# Brd_3_Golden_Ardunio_Schematic.net
KiCad netlist of a schematic drawn in Altium Designer
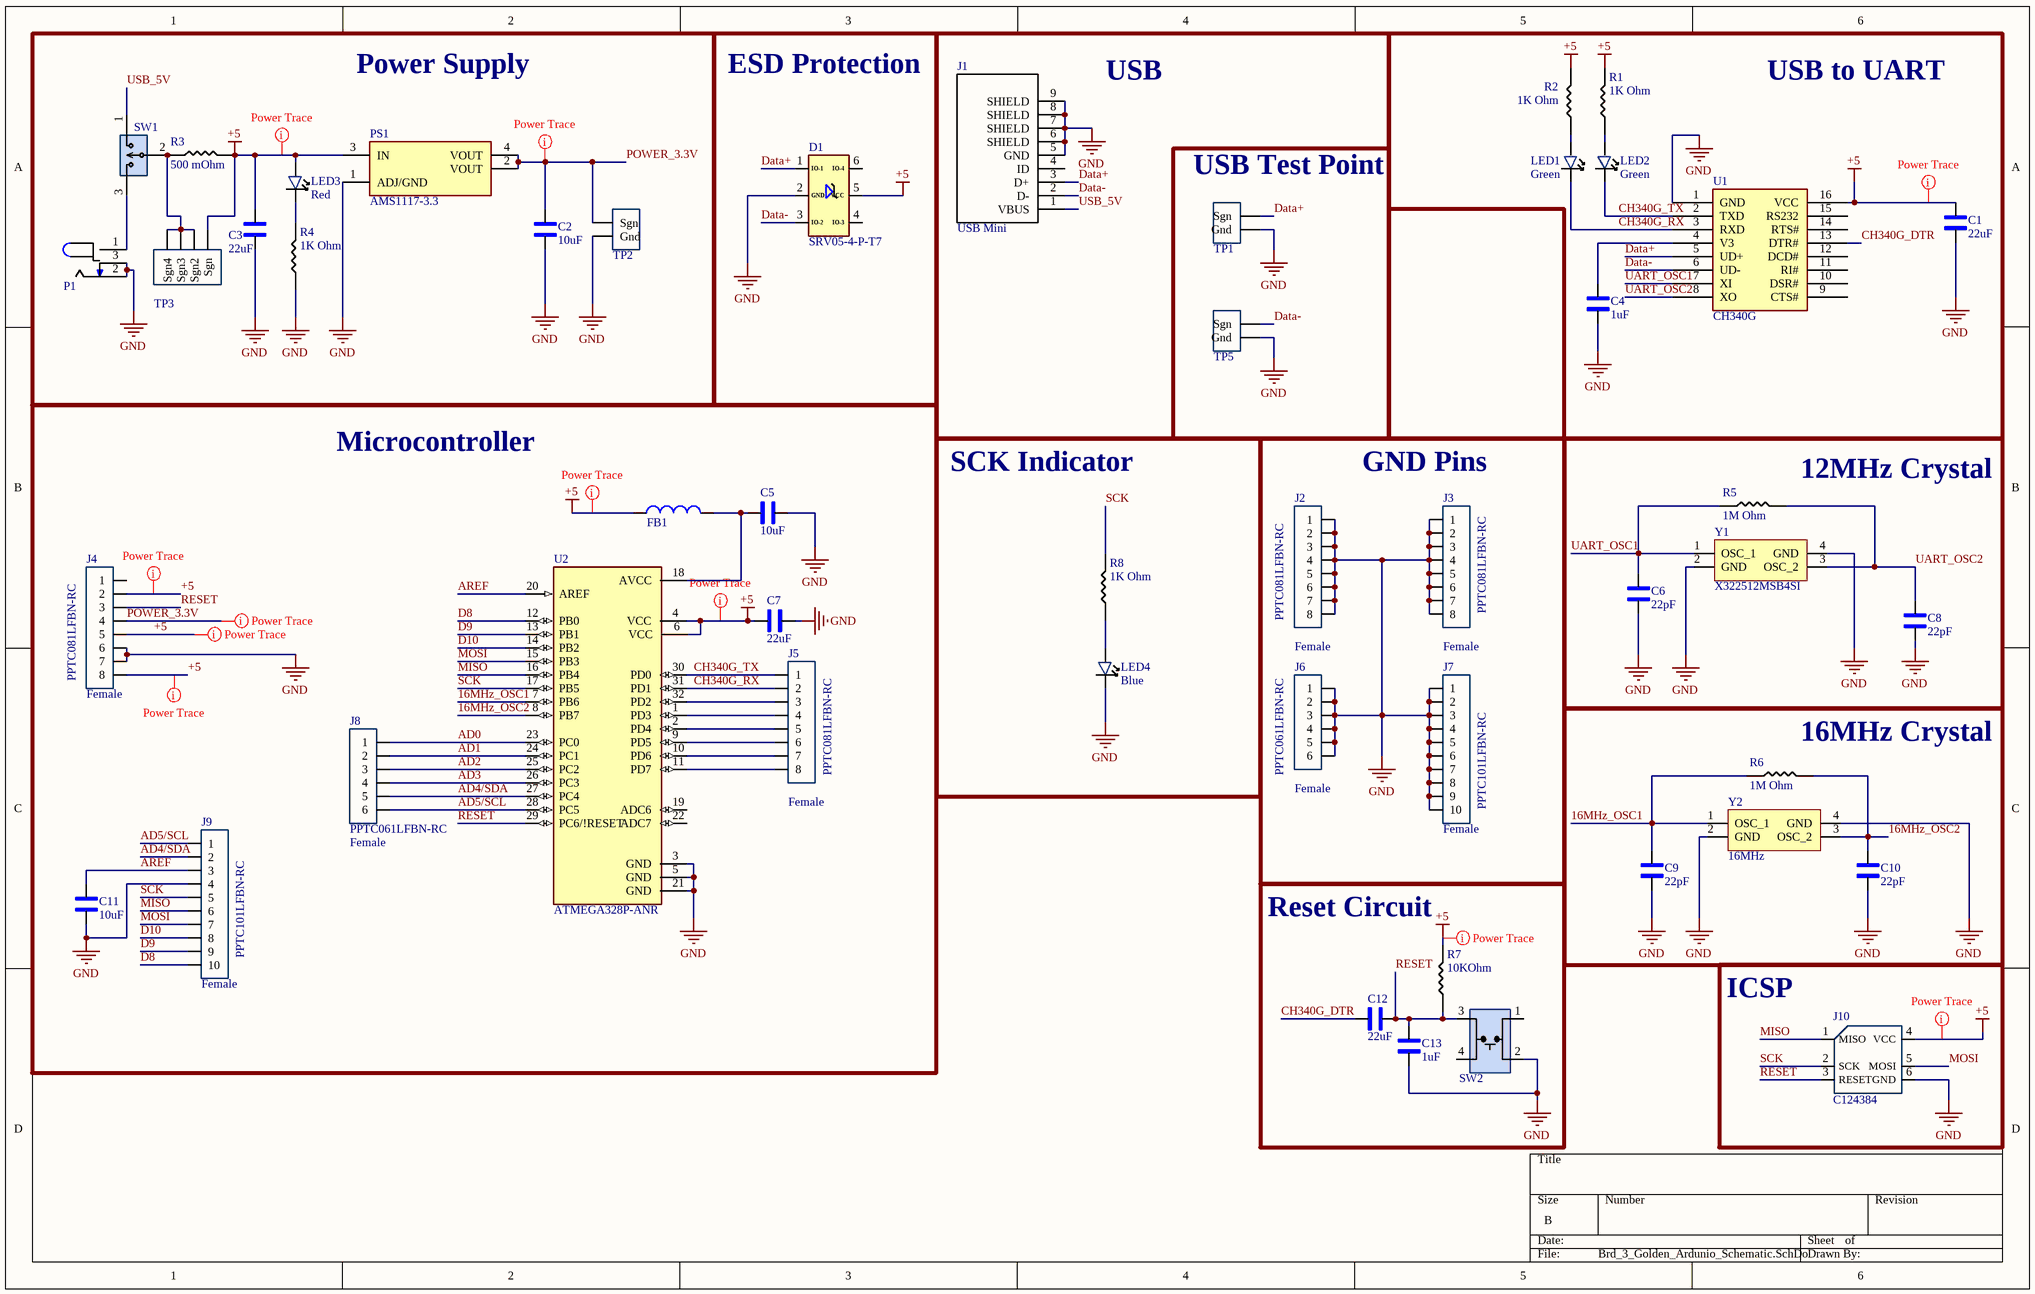
[diagram p0: Brd_3_Golden_Ardunio_Schematic.SchDoc]

(export (version "E")
  (design (tool "Eeschema 10.0.6"))
  (components
    (comp (ref "C1")
      (value "22uF")
      (footprint "0805_Passive_Capaciitor")
      (description "MULTILAYER CERAMIC CAPACITORS MLCC - SMD/SMT 22UF 25V 0805 ROHS")
      (fields (field (name "MFR PART #") "CL21A226MAQNNNE") (field (name "LCSC PART#") "C45783"))
      (libsource (lib "ECEN5730Lib_JLC_2021_08") (part "C_22uF_0805"))
    )
    (comp (ref "C2")
      (value "10uF")
      (footprint "0402_Passive_Capacitor")
      (description "10uF ±20% 6.3V X5R 0402 Multilayer Ceramic Capacitors MLCC - SMD/SMT RoHS")
      (fields (field (name "MFR PART #") "CL05A106MQ5NUNC") (field (name "LCSC PART#") "C15525"))
      (libsource (lib "ECEN5730Lib_JLC_2021_08") (part "C_10uF_0402"))
    )
    (comp (ref "C3")
      (value "22uF")
      (footprint "0805_Passive_Capaciitor")
      (description "MULTILAYER CERAMIC CAPACITORS MLCC - SMD/SMT 22UF 25V 0805 ROHS")
      (fields (field (name "MFR PART #") "CL21A226MAQNNNE") (field (name "LCSC PART#") "C45783"))
      (libsource (lib "ECEN5730Lib_JLC_2021_08") (part "C_22uF_0805"))
    )
    (comp (ref "C4")
      (value "1uF")
      (footprint "0402_Passive_Capacitor")
      (description "MULTILAYER CERAMIC CAPACITORS MLCC - SMD/SMT 1UF 25V 0402 ROHS")
      (fields (field (name "MFR PART #") "CL05A105KA5NQNC") (field (name "LCSC PART#") "C52923"))
      (libsource (lib "ECEN5730Lib_JLC_2021_08") (part "C_1uF_0402"))
    )
    (comp (ref "C5")
      (value "10uF")
      (footprint "0402_Passive_Capacitor")
      (description "10uF ±20% 6.3V X5R 0402 Multilayer Ceramic Capacitors MLCC - SMD/SMT RoHS")
      (fields (field (name "MFR PART #") "CL05A106MQ5NUNC") (field (name "LCSC PART#") "C15525"))
      (libsource (lib "ECEN5730Lib_JLC_2021_08") (part "C_10uF_0402"))
    )
    (comp (ref "C6")
      (value "22pF")
      (footprint "0402_Passive_Capacitor")
      (description "MULTILAYER CERAMIC CAPACITORS MLCC - SMD/SMT 22PF 50V 0402 ROHS")
      (fields (field (name "MFR PART #") "0402CG220J500NT") (field (name "LCSC PART#") "C1555"))
      (libsource (lib "ECEN5730Lib_JLC_2021_08") (part "C_22pF_0402"))
    )
    (comp (ref "C7")
      (value "22uF")
      (footprint "0805_Passive_Capaciitor")
      (description "MULTILAYER CERAMIC CAPACITORS MLCC - SMD/SMT 22UF 25V 0805 ROHS")
      (fields (field (name "MFR PART #") "CL21A226MAQNNNE") (field (name "LCSC PART#") "C45783"))
      (libsource (lib "ECEN5730Lib_JLC_2021_08") (part "C_22uF_0805"))
    )
    (comp (ref "C8")
      (value "22pF")
      (footprint "0402_Passive_Capacitor")
      (description "MULTILAYER CERAMIC CAPACITORS MLCC - SMD/SMT 22PF 50V 0402 ROHS")
      (fields (field (name "MFR PART #") "0402CG220J500NT") (field (name "LCSC PART#") "C1555"))
      (libsource (lib "ECEN5730Lib_JLC_2021_08") (part "C_22pF_0402"))
    )
    (comp (ref "C9")
      (value "22pF")
      (footprint "0402_Passive_Capacitor")
      (description "MULTILAYER CERAMIC CAPACITORS MLCC - SMD/SMT 22PF 50V 0402 ROHS")
      (fields (field (name "MFR PART #") "0402CG220J500NT") (field (name "LCSC PART#") "C1555"))
      (libsource (lib "ECEN5730Lib_JLC_2021_08") (part "C_22pF_0402"))
    )
    (comp (ref "C10")
      (value "22pF")
      (footprint "0402_Passive_Capacitor")
      (description "MULTILAYER CERAMIC CAPACITORS MLCC - SMD/SMT 22PF 50V 0402 ROHS")
      (fields (field (name "MFR PART #") "0402CG220J500NT") (field (name "LCSC PART#") "C1555"))
      (libsource (lib "ECEN5730Lib_JLC_2021_08") (part "C_22pF_0402"))
    )
    (comp (ref "C11")
      (value "10uF")
      (footprint "0402_Passive_Capacitor")
      (description "10uF ±20% 6.3V X5R 0402 Multilayer Ceramic Capacitors MLCC - SMD/SMT RoHS")
      (fields (field (name "MFR PART #") "CL05A106MQ5NUNC") (field (name "LCSC PART#") "C15525"))
      (libsource (lib "ECEN5730Lib_JLC_2021_08") (part "C_10uF_0402"))
    )
    (comp (ref "C12")
      (value "22uF")
      (footprint "0805_Passive_Capaciitor")
      (description "MULTILAYER CERAMIC CAPACITORS MLCC - SMD/SMT 22UF 25V 0805 ROHS")
      (fields (field (name "MFR PART #") "CL21A226MAQNNNE") (field (name "LCSC PART#") "C45783"))
      (libsource (lib "ECEN5730Lib_JLC_2021_08") (part "C_22uF_0805"))
    )
    (comp (ref "C13")
      (value "1uF")
      (footprint "0402_Passive_Capacitor")
      (description "MULTILAYER CERAMIC CAPACITORS MLCC - SMD/SMT 1UF 25V 0402 ROHS")
      (fields (field (name "MFR PART #") "CL05A105KA5NQNC") (field (name "LCSC PART#") "C52923"))
      (libsource (lib "ECEN5730Lib_JLC_2021_08") (part "C_1uF_0402"))
    )
    (comp (ref "D1")
      (value "SRV05-4-P-T7")
      (footprint "TVS")
      (description "TVS SOT-23-6 ROHS")
      (fields (field (name "LCSC PART#") "C85364"))
      (libsource (lib "ECEN5730Lib_JLC_2021_08") (part "D_TVS_Diode"))
    )
    (comp (ref "FB1")
      (value "FB_10uH_0603")
      (footprint "0603_PASSIVE_Capacitor")
      (fields (field (name "MFR PART #") "SDFL1608S100KTF") (field (name "LCSC PART#") "C1035"))
      (libsource (lib "ECEN5730Lib_JLC_2021_08") (part "FB_10uH_0603"))
    )
    (comp (ref "J1")
      (value "USB Mini")
      (footprint "USB_MINI_B")
      (description "Through Hole USB Connectors RoHS")
      (fields (field (name "LCSC PART#") "C46398") (field (name "MFR PART #") "920-462A2021D10102"))
      (libsource (lib "ECEN5730Lib_JLC_2021_08") (part "J_USB_B_Mini"))
    )
    (comp (ref "J2")
      (value "PPTC081LFBN-RC")
      (footprint "8_PIN_ARDUINO_100MIL")
      (description "8 Position Header Connector 0.100\" (2.54mm) Through Hole Tin")
      (fields
        (field (name "DIGIKEY PART") "S7006-ND")
        (field (name "LCSC PART#") "C27438")
        (field (name "ALTIUM_VALUE") "Female")
      )
      (libsource (lib "") (part "JF_8_PIN_FEMALE_ARDUINO_1"))
    )
    (comp (ref "J3")
      (value "PPTC081LFBN-RC")
      (footprint "8_PIN_ARDUINO_100MIL")
      (description "8 Position Header Connector 0.100\" (2.54mm) Through Hole Tin")
      (fields
        (field (name "DIGIKEY PART") "S7006-ND")
        (field (name "LCSC PART#") "C27438")
        (field (name "ALTIUM_VALUE") "Female")
      )
      (libsource (lib "ECEN5730Lib_JLC_2021_08") (part "JF_8_PIN_FEMALE_ARDUINO"))
    )
    (comp (ref "J4")
      (value "PPTC081LFBN-RC")
      (footprint "8_PIN_ARDUINO_100MIL")
      (description "8 Position Header Connector 0.100\" (2.54mm) Through Hole Tin")
      (fields
        (field (name "DIGIKEY PART") "S7006-ND")
        (field (name "LCSC PART#") "C27438")
        (field (name "ALTIUM_VALUE") "Female")
      )
      (libsource (lib "") (part "JF_8_PIN_FEMALE_ARDUINO_1"))
    )
    (comp (ref "J5")
      (value "PPTC081LFBN-RC")
      (footprint "8_PIN_ARDUINO_100MIL")
      (description "8 Position Header Connector 0.100\" (2.54mm) Through Hole Tin")
      (fields
        (field (name "DIGIKEY PART") "S7006-ND")
        (field (name "LCSC PART#") "C27438")
        (field (name "ALTIUM_VALUE") "Female")
      )
      (libsource (lib "ECEN5730Lib_JLC_2021_08") (part "JF_8_PIN_FEMALE_ARDUINO"))
    )
    (comp (ref "J6")
      (value "PPTC061LFBN-RC")
      (footprint "6_PIN_ARDUINO_100mil")
      (description "6 Position Header Connector 0.100\" (2.54mm) Through Hole Tin")
      (fields
        (field (name "DIGIKEY PART") "S7004-ND")
        (field (name "LCSC PART#") "C40877")
        (field (name "ALTIUM_VALUE") "Female")
      )
      (libsource (lib "ECEN5730Lib_JLC_2021_08") (part "JF_6_PIN_FEMALE_ARDUINO"))
    )
    (comp (ref "J7")
      (value "PPTC101LFBN-RC")
      (footprint "10_PIN_ARDUINO_100MIL")
      (description "10 Position Header Connector 0.100\" (2.54mm) Through Hole Tin")
      (fields
        (field (name "DIGIKEY PART") "S7008-ND")
        (field (name "LCSC PART#") "C225507")
        (field (name "ALTIUM_VALUE") "Female")
      )
      (libsource (lib "ECEN5730Lib_JLC_2021_08") (part "JF_10_PIN_FEMALE_ARDUINO"))
    )
    (comp (ref "J8")
      (value "PPTC061LFBN-RC")
      (footprint "6_PIN_ARDUINO_100mil")
      (description "6 Position Header Connector 0.100\" (2.54mm) Through Hole Tin")
      (fields
        (field (name "DIGIKEY PART") "S7004-ND")
        (field (name "LCSC PART#") "C40877")
        (field (name "ALTIUM_VALUE") "Female")
      )
      (libsource (lib "ECEN5730Lib_JLC_2021_08") (part "JF_6_PIN_FEMALE_ARDUINO"))
    )
    (comp (ref "J9")
      (value "PPTC101LFBN-RC")
      (footprint "10_PIN_ARDUINO_100MIL")
      (description "10 Position Header Connector 0.100\" (2.54mm) Through Hole Tin")
      (fields
        (field (name "DIGIKEY PART") "S7008-ND")
        (field (name "LCSC PART#") "C225507")
        (field (name "ALTIUM_VALUE") "Female")
      )
      (libsource (lib "ECEN5730Lib_JLC_2021_08") (part "JF_10_PIN_FEMALE_ARDUINO"))
    )
    (comp (ref "J10")
      (value "NRPN032PAEN-RC")
      (footprint "ICSP")
      (description "Connector Header Through Hole 6 position 0.079\" (2.00mm)")
      (fields (field (name "DIGIKEY PART") "S5801-03-ND") (field (name "LCSC PART#") "C124384"))
      (libsource (lib "ECEN5730Lib_JLC_2021_08") (part "J_ICSP"))
    )
    (comp (ref "LED1")
      (value "Green")
      (footprint "LED_0603")
      (description "LIGHT EMITTING DIODES (LED) GREEN 520~535NM 112~258MCD@20MA TOP VIEW 0603 ROHS")
      (fields (field (name "MFR PART #") "19-217/GHC-YR1S2/3T") (field (name "LCSC PART#") "C72043"))
      (libsource (lib "ECEN5730Lib_JLC_2021_08") (part "LED_GREEN_0603"))
    )
    (comp (ref "LED2")
      (value "Green")
      (footprint "LED_0603")
      (description "LIGHT EMITTING DIODES (LED) GREEN 520~535NM 112~258MCD@20MA TOP VIEW 0603 ROHS")
      (fields (field (name "MFR PART #") "19-217/GHC-YR1S2/3T") (field (name "LCSC PART#") "C72043"))
      (libsource (lib "ECEN5730Lib_JLC_2021_08") (part "LED_GREEN_0603"))
    )
    (comp (ref "LED3")
      (value "Red")
      (footprint "LED_0603")
      (description "LIGHT EMITTING DIODES (LED) RED 520~625NM 90~100MCD@20MA TOP VIEW 0603 ROHS")
      (fields (field (name "MFR PART #") "KT-0603R") (field (name "LCSC PART#") "C2286"))
      (libsource (lib "ECEN5730Lib_JLC_2021_08") (part "LED_RED_0603"))
    )
    (comp (ref "LED4")
      (value "Blue")
      (footprint "LED_0603")
      (description "LIGHT EMITTING DIODES (LED) BLUE 465~475NM 11.5~28.5MCD@5MA TOP VIEW 0603 ROHS")
      (fields (field (name "MFR PART #") "19-217/BHC-ZL1M2RY/3T") (field (name "LCSC PART#") "C72041"))
      (libsource (lib "ECEN5730Lib_JLC_2021_08") (part "LED_BLUE_0603"))
    )
    (comp (ref "P1")
      (value "Power Jack")
      (footprint "Power_Jack")
      (description "Power Barrel Connector Jack 2.10mm ID (0.083\"), 5.50mm OD (0.217\") Through Hole, Right Angle")
      (fields (field (name "DIGIKEY PART") "CP-102A-ND") (field (name "LCSC PART#") "C136744"))
      (libsource (lib "ECEN5730Lib_JLC_2021_08") (part "P_Power Jack"))
    )
    (comp (ref "PS1")
      (value "AMS1117-3.3")
      (footprint "LDO")
      (description "LOW DROPOUT REGULATORS(LDO) POSITIVE FIXED 1.3V @ 800MA 15V 3.3V 1A SOT-223 ROHS")
      (fields (field (name "LCSC PART#") "C6186"))
      (libsource (lib "ECEN5730Lib_JLC_2021_08") (part "PS_AMS_LDO_3v3"))
    )
    (comp (ref "R1")
      (value "1K Ohm")
      (footprint "0402_Passive_Resistor")
      (description "1 kOhms chip resistor SURFACE MOUNT 1KOHMS ±1% 1/16W 0402 ROHS")
      (fields (field (name "MFR PART #") "0402WGF1001TCE") (field (name "LCSC PART#") "C11702"))
      (libsource (lib "ECEN5730Lib_JLC_2021_08") (part "R_1K_0402"))
    )
    (comp (ref "R2")
      (value "1K Ohm")
      (footprint "0402_Passive_Resistor")
      (description "1 kOhms chip resistor SURFACE MOUNT 1KOHMS ±1% 1/16W 0402 ROHS")
      (fields (field (name "MFR PART #") "0402WGF1001TCE") (field (name "LCSC PART#") "C11702"))
      (libsource (lib "ECEN5730Lib_JLC_2021_08") (part "R_1K_0402"))
    )
    (comp (ref "R3")
      (value "500 mOhm")
      (footprint "0603_PASSIVE_Resistor")
      (description "CHIP RESISTOR - SURFACE MOUNT 0.5OHMS ±1% 1/10W 0603 ROHS")
      (fields (field (name "MFR PART #") "0603WAF500LT5E") (field (name "LCSC PART#") "C45312"))
      (libsource (lib "ECEN5730Lib_JLC_2021_08") (part "R_500m_0603"))
    )
    (comp (ref "R4")
      (value "1K Ohm")
      (footprint "0402_Passive_Resistor")
      (description "1 kOhms chip resistor SURFACE MOUNT 1KOHMS ±1% 1/16W 0402 ROHS")
      (fields (field (name "MFR PART #") "0402WGF1001TCE") (field (name "LCSC PART#") "C11702"))
      (libsource (lib "ECEN5730Lib_JLC_2021_08") (part "R_1K_0402"))
    )
    (comp (ref "R5")
      (value "1M Ohm")
      (footprint "1206_Passive_Resitor")
      (description "CHIP RESISTOR - SURFACE MOUNT 1MOHMS ±1% 1/4W 1206 ROHS")
      (fields (field (name "DIGIKEY PART") "Number RMCF1206JT1M00CT-ND") (field (name "LCSC PART#") "C17927"))
      (libsource (lib "ECEN5730Lib_JLC_2021_08") (part "R_1M_1206"))
    )
    (comp (ref "R6")
      (value "1M Ohm")
      (footprint "1206_Passive_Resitor")
      (description "CHIP RESISTOR - SURFACE MOUNT 1MOHMS ±1% 1/4W 1206 ROHS")
      (fields (field (name "DIGIKEY PART") "Number RMCF1206JT1M00CT-ND") (field (name "LCSC PART#") "C17927"))
      (libsource (lib "ECEN5730Lib_JLC_2021_08") (part "R_1M_1206"))
    )
    (comp (ref "R7")
      (value "10KOhm")
      (footprint "0402_Passive_Resistor")
      (description "CHIP RESISTOR - SURFACE MOUNT 10KOHMS ±1% 1/16W 0402 ROHS")
      (fields (field (name "MFR PART #") "0402WGF1002TCE") (field (name "LCSC PART#") "C25744"))
      (libsource (lib "ECEN5730Lib_JLC_2021_08") (part "R_10KOhm_0402"))
    )
    (comp (ref "R8")
      (value "1K Ohm")
      (footprint "0402_Passive_Resistor")
      (description "1 kOhms chip resistor SURFACE MOUNT 1KOHMS ±1% 1/16W 0402 ROHS")
      (fields (field (name "MFR PART #") "0402WGF1001TCE") (field (name "LCSC PART#") "C11702"))
      (libsource (lib "ECEN5730Lib_JLC_2021_08") (part "R_1K_0402"))
    )
    (comp (ref "SW1")
      (value "PREC003SAAN-RC")
      (footprint "3_PIN_100mil")
      (description "Connector Header Through Hole 3 position 0.100\" (2.54mm)")
      (fields (field (name "DIGIKEY PART") "S1012EC-03-ND") (field (name "LCSC PART#") "C429954"))
      (libsource (lib "ECEN5730Lib_JLC_2021_08") (part "SW_3Pin_100mil_Switch"))
    )
    (comp (ref "SW2")
      (value "TL3305AF160QG")
      (footprint "Switch_JLC")
      (description "Tactile Switch SPST-NO Top Actuated Surface Mount")
      (fields (field (name "MFR PART #") "C174049"))
      (libsource (lib "ECEN5730Lib_JLC_2021_08") (part "SW_Push_Button_JLC"))
    )
    (comp (ref "TP1")
      (value "10x Probe TP")
      (footprint "TP10x_Probe")
      (description "Test Point 300 mil centers")
      (libsource (lib "ECEN5730Lib_Manual_2021_08") (part "TP_10x_Probe"))
    )
    (comp (ref "TP2")
      (value "10x Probe TP")
      (footprint "TP10x_Probe")
      (description "Test Point 300 mil centers")
      (libsource (lib "") (part "TP_10x_Probe_1"))
    )
    (comp (ref "TP3")
      (value "10x Probe Floating TP")
      (footprint "TP10x_Floating")
      (description "Test Point 300 mil centers")
      (libsource (lib "ECEN5730Lib_Manual_2021_08") (part "TP_10x_Floating"))
    )
    (comp (ref "TP5")
      (value "10x Probe TP")
      (footprint "TP10x_Probe")
      (description "Test Point 300 mil centers")
      (libsource (lib "ECEN5730Lib_Manual_2021_08") (part "TP_10x_Probe"))
    )
    (comp (ref "U1")
      (value "CH340G")
      (footprint "USB to serial")
      (description "Transceiver USB 2.0 2Mbps SOP-16_150mil USB ICs RoHS")
      (fields (field (name "LCSC PART#") "C14267"))
      (libsource (lib "ECEN5730Lib_JLC_2021_08") (part "U_USBtoSerial"))
    )
    (comp (ref "U2")
      (value "ATMEGA328P-ANR")
      (footprint "ATMega328P")
      (description "AVR AVR® ATmega Microcontroller IC 8-Bit 20MHz 32KB (16K x 16) FLASH 32-TQFP (7x7)")
      (fields (field (name "MFR PART #") "ATMEGA328P-AU") (field (name "LCSC PART#") "C14877"))
      (libsource (lib "ECEN5730Lib_JLC_2021_08") (part "U_ATMega328P"))
    )
    (comp (ref "Y1")
      (value "X322512MSB4SI")
      (footprint "Crystal resonator")
      (description "SMD Crystal Resonators 12MHz ±10ppm SMD-3225_4P RoHS")
      (fields (field (name "LCSC PART#") "C9002"))
      (libsource (lib "ECEN5730Lib_JLC_2021_08") (part "X_12MHz_Res"))
    )
    (comp (ref "Y2")
      (value "16MHz")
      (footprint "Crystal resonator")
      (description "±10ppm 16000000Hz -40℃~85℃ 贴片无源晶振 60Ω 9pF SMD3225-4P Crystals ROHS")
      (fields (field (name "LCSC PART#") "C13738") (field (name "MFR PART #") "X322516MLB4SI"))
      (libsource (lib "ECEN5730Lib_JLC_2021_08") (part "X_16Mhz_Res"))
    )
  )
  (nets
    (net (code "1") (name "+5") (class "Default")
      (node (ref "C1") (pin "2") (pinfunction "2_2") (pintype "passive"))
      (node (ref "C3") (pin "2") (pinfunction "2_2") (pintype "passive"))
      (node (ref "C7") (pin "1") (pinfunction "1_1") (pintype "passive"))
      (node (ref "D1") (pin "5") (pinfunction "VCC_5") (pintype "passive"))
      (node (ref "FB1") (pin "1") (pinfunction "1_1") (pintype "passive"))
      (node (ref "J10") (pin "4") (pinfunction "VCC_4") (pintype "passive"))
      (node (ref "J4") (pin "2") (pinfunction "2_2") (pintype "passive"))
      (node (ref "J4") (pin "5") (pinfunction "5_5") (pintype "passive"))
      (node (ref "J4") (pin "8") (pinfunction "8_8") (pintype "passive"))
      (node (ref "LED3") (pin "1") (pinfunction "1_1") (pintype "passive"))
      (node (ref "PS1") (pin "3") (pinfunction "IN_3") (pintype "power_in"))
      (node (ref "R1") (pin "2") (pinfunction "2_2") (pintype "passive"))
      (node (ref "R2") (pin "2") (pinfunction "2_2") (pintype "passive"))
      (node (ref "R3") (pin "2") (pinfunction "2_2") (pintype "passive"))
      (node (ref "R7") (pin "2") (pinfunction "2_2") (pintype "passive"))
      (node (ref "TP3") (pin "1") (pinfunction "Sgn_1") (pintype "passive"))
      (node (ref "U1") (pin "16") (pinfunction "VCC_16") (pintype "passive"))
      (node (ref "U2") (pin "4") (pinfunction "VCC_4") (pintype "power_in"))
      (node (ref "U2") (pin "6") (pinfunction "VCC_6") (pintype "power_in"))
    )
    (net (code "2") (name "/16MHz_OSC1") (class "Default")
      (node (ref "C9") (pin "2") (pinfunction "2_2") (pintype "passive"))
      (node (ref "R6") (pin "1") (pinfunction "1_1") (pintype "passive"))
      (node (ref "U2") (pin "7") (pinfunction "PB6_7") (pintype "bidirectional"))
      (node (ref "Y2") (pin "1") (pinfunction "OSC_1_1") (pintype "passive"))
    )
    (net (code "3") (name "/16MHz_OSC2") (class "Default")
      (node (ref "C10") (pin "2") (pinfunction "2_2") (pintype "passive"))
      (node (ref "R6") (pin "2") (pinfunction "2_2") (pintype "passive"))
      (node (ref "U2") (pin "8") (pinfunction "PB7_8") (pintype "bidirectional"))
      (node (ref "Y2") (pin "3") (pinfunction "OSC_2_3") (pintype "passive"))
    )
    (net (code "4") (name "/AD0") (class "Default")
      (node (ref "J8") (pin "1") (pinfunction "1_1") (pintype "passive"))
      (node (ref "U2") (pin "23") (pinfunction "PC0_23") (pintype "bidirectional"))
    )
    (net (code "5") (name "/AD1") (class "Default")
      (node (ref "J8") (pin "2") (pinfunction "2_2") (pintype "passive"))
      (node (ref "U2") (pin "24") (pinfunction "PC1_24") (pintype "bidirectional"))
    )
    (net (code "6") (name "/AD2") (class "Default")
      (node (ref "J8") (pin "3") (pinfunction "3_3") (pintype "passive"))
      (node (ref "U2") (pin "25") (pinfunction "PC2_25") (pintype "bidirectional"))
    )
    (net (code "7") (name "/AD3") (class "Default")
      (node (ref "J8") (pin "4") (pinfunction "4_4") (pintype "passive"))
      (node (ref "U2") (pin "26") (pinfunction "PC3_26") (pintype "bidirectional"))
    )
    (net (code "8") (name "/AD4{slash}SDA") (class "Default")
      (node (ref "J8") (pin "5") (pinfunction "5_5") (pintype "passive"))
      (node (ref "J9") (pin "2") (pinfunction "2_2") (pintype "passive"))
      (node (ref "U2") (pin "27") (pinfunction "PC4_27") (pintype "bidirectional"))
    )
    (net (code "9") (name "/AD5{slash}SCL") (class "Default")
      (node (ref "J8") (pin "6") (pinfunction "6_6") (pintype "passive"))
      (node (ref "J9") (pin "1") (pinfunction "1_1") (pintype "passive"))
      (node (ref "U2") (pin "28") (pinfunction "PC5_28") (pintype "bidirectional"))
    )
    (net (code "10") (name "/AREF") (class "Default")
      (node (ref "C11") (pin "2") (pinfunction "2_2") (pintype "passive"))
      (node (ref "J9") (pin "3") (pinfunction "3_3") (pintype "passive"))
      (node (ref "U2") (pin "20") (pinfunction "AREF_20") (pintype "input"))
    )
    (net (code "11") (name "/CH340G_DTR") (class "Default")
      (node (ref "C12") (pin "1") (pinfunction "1_1") (pintype "passive"))
      (node (ref "U1") (pin "13") (pinfunction "DTR#_13") (pintype "passive"))
    )
    (net (code "12") (name "/CH340G_RX") (class "Default")
      (node (ref "J5") (pin "2") (pinfunction "2_2") (pintype "passive"))
      (node (ref "LED1") (pin "2") (pinfunction "2_2") (pintype "passive"))
      (node (ref "U1") (pin "3") (pinfunction "RXD_3") (pintype "passive"))
      (node (ref "U2") (pin "31") (pinfunction "PD1_31") (pintype "bidirectional"))
    )
    (net (code "13") (name "/CH340G_TX") (class "Default")
      (node (ref "J5") (pin "1") (pinfunction "1_1") (pintype "passive"))
      (node (ref "LED2") (pin "2") (pinfunction "2_2") (pintype "passive"))
      (node (ref "U1") (pin "2") (pinfunction "TXD_2") (pintype "passive"))
      (node (ref "U2") (pin "30") (pinfunction "PD0_30") (pintype "bidirectional"))
    )
    (net (code "14") (name "/D8") (class "Default")
      (node (ref "J9") (pin "10") (pinfunction "10_10") (pintype "passive"))
      (node (ref "U2") (pin "12") (pinfunction "PB0_12") (pintype "bidirectional"))
    )
    (net (code "15") (name "/D9") (class "Default")
      (node (ref "J9") (pin "9") (pinfunction "9_9") (pintype "passive"))
      (node (ref "U2") (pin "13") (pinfunction "PB1_13") (pintype "bidirectional"))
    )
    (net (code "16") (name "/D10") (class "Default")
      (node (ref "J9") (pin "8") (pinfunction "8_8") (pintype "passive"))
      (node (ref "U2") (pin "14") (pinfunction "PB2_14") (pintype "bidirectional"))
    )
    (net (code "17") (name "/Data+") (class "Default")
      (node (ref "D1") (pin "1") (pinfunction "IO-1_1") (pintype "passive"))
      (node (ref "J1") (pin "3") (pinfunction "D+_3") (pintype "passive"))
      (node (ref "TP1") (pin "1") (pinfunction "Sgn_1") (pintype "passive"))
      (node (ref "U1") (pin "5") (pinfunction "UD+_5") (pintype "passive"))
    )
    (net (code "18") (name "/Data-") (class "Default")
      (node (ref "D1") (pin "3") (pinfunction "IO-2_3") (pintype "passive"))
      (node (ref "J1") (pin "2") (pinfunction "D-_2") (pintype "passive"))
      (node (ref "TP5") (pin "1") (pinfunction "Sgn_1") (pintype "passive"))
      (node (ref "U1") (pin "6") (pinfunction "UD-_6") (pintype "passive"))
    )
    (net (code "19") (name "/MISO") (class "Default")
      (node (ref "J10") (pin "1") (pinfunction "MISO_1") (pintype "passive"))
      (node (ref "J9") (pin "6") (pinfunction "6_6") (pintype "passive"))
      (node (ref "U2") (pin "16") (pinfunction "PB4_16") (pintype "bidirectional"))
    )
    (net (code "20") (name "/MOSI") (class "Default")
      (node (ref "J10") (pin "5") (pinfunction "MOSI_5") (pintype "passive"))
      (node (ref "J9") (pin "7") (pinfunction "7_7") (pintype "passive"))
      (node (ref "U2") (pin "15") (pinfunction "PB3_15") (pintype "bidirectional"))
    )
    (net (code "21") (name "/POWER_3.3V") (class "Default")
      (node (ref "C2") (pin "2") (pinfunction "2_2") (pintype "passive"))
      (node (ref "J4") (pin "4") (pinfunction "4_4") (pintype "passive"))
      (node (ref "PS1") (pin "2") (pinfunction "VOUT_2") (pintype "power_in"))
      (node (ref "PS1") (pin "4") (pinfunction "VOUT_4") (pintype "power_in"))
      (node (ref "TP2") (pin "1") (pinfunction "Sgn_1") (pintype "passive"))
    )
    (net (code "22") (name "/RESET") (class "Default")
      (node (ref "C12") (pin "2") (pinfunction "2_2") (pintype "passive"))
      (node (ref "C13") (pin "2") (pinfunction "2_2") (pintype "passive"))
      (node (ref "J10") (pin "3") (pinfunction "RESET_3") (pintype "passive"))
      (node (ref "J4") (pin "3") (pinfunction "3_3") (pintype "passive"))
      (node (ref "R7") (pin "1") (pinfunction "1_1") (pintype "passive"))
      (node (ref "SW2") (pin "3") (pinfunction "3_3") (pintype "passive"))
      (node (ref "U2") (pin "29") (pinfunction "PC6/!RESET_29") (pintype "bidirectional"))
    )
    (net (code "23") (name "/SCK") (class "Default")
      (node (ref "J10") (pin "2") (pinfunction "SCK_2") (pintype "passive"))
      (node (ref "J9") (pin "5") (pinfunction "5_5") (pintype "passive"))
      (node (ref "R8") (pin "2") (pinfunction "2_2") (pintype "passive"))
      (node (ref "U2") (pin "17") (pinfunction "PB5_17") (pintype "bidirectional"))
    )
    (net (code "24") (name "/UART_OSC1") (class "Default")
      (node (ref "C6") (pin "2") (pinfunction "2_2") (pintype "passive"))
      (node (ref "R5") (pin "1") (pinfunction "1_1") (pintype "passive"))
      (node (ref "U1") (pin "7") (pinfunction "XI_7") (pintype "passive"))
      (node (ref "Y1") (pin "1") (pinfunction "OSC_1_1") (pintype "passive"))
    )
    (net (code "25") (name "/UART_OSC2") (class "Default")
      (node (ref "C8") (pin "2") (pinfunction "2_2") (pintype "passive"))
      (node (ref "R5") (pin "2") (pinfunction "2_2") (pintype "passive"))
      (node (ref "U1") (pin "8") (pinfunction "XO_8") (pintype "passive"))
      (node (ref "Y1") (pin "3") (pinfunction "OSC_2_3") (pintype "passive"))
    )
    (net (code "26") (name "/USB_5V") (class "Default")
      (node (ref "J1") (pin "1") (pinfunction "VBUS_1") (pintype "passive"))
      (node (ref "SW1") (pin "1") (pinfunction "1_1") (pintype "passive"))
    )
    (net (code "27") (name "GND") (class "Default")
      (node (ref "C1") (pin "1") (pinfunction "1_1") (pintype "passive"))
      (node (ref "C10") (pin "1") (pinfunction "1_1") (pintype "passive"))
      (node (ref "C11") (pin "1") (pinfunction "1_1") (pintype "passive"))
      (node (ref "C13") (pin "1") (pinfunction "1_1") (pintype "passive"))
      (node (ref "C2") (pin "1") (pinfunction "1_1") (pintype "passive"))
      (node (ref "C3") (pin "1") (pinfunction "1_1") (pintype "passive"))
      (node (ref "C4") (pin "1") (pinfunction "1_1") (pintype "passive"))
      (node (ref "C5") (pin "2") (pinfunction "2_2") (pintype "passive"))
      (node (ref "C6") (pin "1") (pinfunction "1_1") (pintype "passive"))
      (node (ref "C7") (pin "2") (pinfunction "2_2") (pintype "passive"))
      (node (ref "C8") (pin "1") (pinfunction "1_1") (pintype "passive"))
      (node (ref "C9") (pin "1") (pinfunction "1_1") (pintype "passive"))
      (node (ref "D1") (pin "2") (pinfunction "GND_2") (pintype "passive"))
      (node (ref "J1") (pin "5") (pinfunction "GND_5") (pintype "passive"))
      (node (ref "J1") (pin "6") (pinfunction "SHIELD_6") (pintype "passive"))
      (node (ref "J1") (pin "7") (pinfunction "SHIELD_7") (pintype "passive"))
      (node (ref "J1") (pin "8") (pinfunction "SHIELD_8") (pintype "passive"))
      (node (ref "J1") (pin "9") (pinfunction "SHIELD_9") (pintype "passive"))
      (node (ref "J10") (pin "6") (pinfunction "GND_6") (pintype "passive"))
      (node (ref "J2") (pin "1") (pinfunction "1_1") (pintype "passive"))
      (node (ref "J2") (pin "2") (pinfunction "2_2") (pintype "passive"))
      (node (ref "J2") (pin "3") (pinfunction "3_3") (pintype "passive"))
      (node (ref "J2") (pin "4") (pinfunction "4_4") (pintype "passive"))
      (node (ref "J2") (pin "5") (pinfunction "5_5") (pintype "passive"))
      (node (ref "J2") (pin "6") (pinfunction "6_6") (pintype "passive"))
      (node (ref "J2") (pin "7") (pinfunction "7_7") (pintype "passive"))
      (node (ref "J2") (pin "8") (pinfunction "8_8") (pintype "passive"))
      (node (ref "J3") (pin "1") (pinfunction "1_1") (pintype "passive"))
      (node (ref "J3") (pin "2") (pinfunction "2_2") (pintype "passive"))
      (node (ref "J3") (pin "3") (pinfunction "3_3") (pintype "passive"))
      (node (ref "J3") (pin "4") (pinfunction "4_4") (pintype "passive"))
      (node (ref "J3") (pin "5") (pinfunction "5_5") (pintype "passive"))
      (node (ref "J3") (pin "6") (pinfunction "6_6") (pintype "passive"))
      (node (ref "J3") (pin "7") (pinfunction "7_7") (pintype "passive"))
      (node (ref "J3") (pin "8") (pinfunction "8_8") (pintype "passive"))
      (node (ref "J4") (pin "6") (pinfunction "6_6") (pintype "passive"))
      (node (ref "J4") (pin "7") (pinfunction "7_7") (pintype "passive"))
      (node (ref "J6") (pin "1") (pinfunction "1_1") (pintype "passive"))
      (node (ref "J6") (pin "2") (pinfunction "2_2") (pintype "passive"))
      (node (ref "J6") (pin "3") (pinfunction "3_3") (pintype "passive"))
      (node (ref "J6") (pin "4") (pinfunction "4_4") (pintype "passive"))
      (node (ref "J6") (pin "5") (pinfunction "5_5") (pintype "passive"))
      (node (ref "J6") (pin "6") (pinfunction "6_6") (pintype "passive"))
      (node (ref "J7") (pin "1") (pinfunction "1_1") (pintype "passive"))
      (node (ref "J7") (pin "10") (pinfunction "10_10") (pintype "passive"))
      (node (ref "J7") (pin "2") (pinfunction "2_2") (pintype "passive"))
      (node (ref "J7") (pin "3") (pinfunction "3_3") (pintype "passive"))
      (node (ref "J7") (pin "4") (pinfunction "4_4") (pintype "passive"))
      (node (ref "J7") (pin "5") (pinfunction "5_5") (pintype "passive"))
      (node (ref "J7") (pin "6") (pinfunction "6_6") (pintype "passive"))
      (node (ref "J7") (pin "7") (pinfunction "7_7") (pintype "passive"))
      (node (ref "J7") (pin "8") (pinfunction "8_8") (pintype "passive"))
      (node (ref "J7") (pin "9") (pinfunction "9_9") (pintype "passive"))
      (node (ref "J9") (pin "4") (pinfunction "4_4") (pintype "passive"))
      (node (ref "LED4") (pin "2") (pinfunction "2_2") (pintype "passive"))
      (node (ref "P1") (pin "2") (pinfunction "2_2") (pintype "power_in"))
      (node (ref "P1") (pin "3") (pinfunction "3_3") (pintype "power_in"))
      (node (ref "PS1") (pin "1") (pinfunction "ADJ/GND_1") (pintype "passive"))
      (node (ref "R4") (pin "1") (pinfunction "1_1") (pintype "passive"))
      (node (ref "SW2") (pin "2") (pinfunction "2_2") (pintype "passive"))
      (node (ref "TP1") (pin "2") (pinfunction "Gnd_2") (pintype "passive"))
      (node (ref "TP2") (pin "2") (pinfunction "Gnd_2") (pintype "passive"))
      (node (ref "TP5") (pin "2") (pinfunction "Gnd_2") (pintype "passive"))
      (node (ref "U1") (pin "1") (pinfunction "GND_1") (pintype "passive"))
      (node (ref "U2") (pin "21") (pinfunction "GND_21") (pintype "power_in"))
      (node (ref "U2") (pin "3") (pinfunction "GND_3") (pintype "power_in"))
      (node (ref "U2") (pin "5") (pinfunction "GND_5") (pintype "power_in"))
      (node (ref "Y1") (pin "2") (pinfunction "GND_2") (pintype "passive"))
      (node (ref "Y1") (pin "4") (pinfunction "GND_4") (pintype "passive"))
      (node (ref "Y2") (pin "2") (pinfunction "GND_2") (pintype "passive"))
      (node (ref "Y2") (pin "4") (pinfunction "GND_4") (pintype "passive"))
    )
    (net (code "28") (name "Net-(LED1-Pad1)") (class "Default")
      (node (ref "LED1") (pin "1") (pinfunction "1_1") (pintype "passive"))
      (node (ref "R2") (pin "1") (pinfunction "1_1") (pintype "passive"))
    )
    (net (code "29") (name "Net-(LED2-Pad1)") (class "Default")
      (node (ref "LED2") (pin "1") (pinfunction "1_1") (pintype "passive"))
      (node (ref "R1") (pin "1") (pinfunction "1_1") (pintype "passive"))
    )
    (net (code "30") (name "Net-(LED3-Pad2)") (class "Default")
      (node (ref "LED3") (pin "2") (pinfunction "2_2") (pintype "passive"))
      (node (ref "R4") (pin "2") (pinfunction "2_2") (pintype "passive"))
    )
    (net (code "31") (name "Net-(LED4-Pad1)") (class "Default")
      (node (ref "LED4") (pin "1") (pinfunction "1_1") (pintype "passive"))
      (node (ref "R8") (pin "1") (pinfunction "1_1") (pintype "passive"))
    )
    (net (code "32") (name "Net-(P1-Pad1)") (class "Default")
      (node (ref "P1") (pin "1") (pinfunction "1_1") (pintype "power_in"))
      (node (ref "SW1") (pin "3") (pinfunction "3_3") (pintype "passive"))
    )
    (net (code "33") (name "Net-(TP3-Sgn2)") (class "Default")
      (node (ref "R3") (pin "1") (pinfunction "1_1") (pintype "passive"))
      (node (ref "SW1") (pin "2") (pinfunction "2_2") (pintype "passive"))
      (node (ref "TP3") (pin "2") (pinfunction "Sgn2_2") (pintype "passive"))
      (node (ref "TP3") (pin "3") (pinfunction "Sgn3_3") (pintype "passive"))
      (node (ref "TP3") (pin "4") (pinfunction "Sgn4_4") (pintype "passive"))
    )
    (net (code "34") (name "Net-(U1-V3)") (class "Default")
      (node (ref "C4") (pin "2") (pinfunction "2_2") (pintype "passive"))
      (node (ref "U1") (pin "4") (pinfunction "V3_4") (pintype "passive"))
    )
    (net (code "35") (name "Net-(U2-AVCC)") (class "Default")
      (node (ref "C5") (pin "1") (pinfunction "1_1") (pintype "passive"))
      (node (ref "FB1") (pin "2") (pinfunction "2_2") (pintype "passive"))
      (node (ref "U2") (pin "18") (pinfunction "AVCC_18") (pintype "power_in"))
    )
    (net (code "36") (name "Net-(U2-PD2)") (class "Default")
      (node (ref "J5") (pin "3") (pinfunction "3_3") (pintype "passive"))
      (node (ref "U2") (pin "32") (pinfunction "PD2_32") (pintype "bidirectional"))
    )
    (net (code "37") (name "Net-(U2-PD3)") (class "Default")
      (node (ref "J5") (pin "4") (pinfunction "4_4") (pintype "passive"))
      (node (ref "U2") (pin "1") (pinfunction "PD3_1") (pintype "bidirectional"))
    )
    (net (code "38") (name "Net-(U2-PD4)") (class "Default")
      (node (ref "J5") (pin "5") (pinfunction "5_5") (pintype "passive"))
      (node (ref "U2") (pin "2") (pinfunction "PD4_2") (pintype "bidirectional"))
    )
    (net (code "39") (name "Net-(U2-PD5)") (class "Default")
      (node (ref "J5") (pin "6") (pinfunction "6_6") (pintype "passive"))
      (node (ref "U2") (pin "9") (pinfunction "PD5_9") (pintype "bidirectional"))
    )
    (net (code "40") (name "Net-(U2-PD6)") (class "Default")
      (node (ref "J5") (pin "7") (pinfunction "7_7") (pintype "passive"))
      (node (ref "U2") (pin "10") (pinfunction "PD6_10") (pintype "bidirectional"))
    )
    (net (code "41") (name "Net-(U2-PD7)") (class "Default")
      (node (ref "J5") (pin "8") (pinfunction "8_8") (pintype "passive"))
      (node (ref "U2") (pin "11") (pinfunction "PD7_11") (pintype "bidirectional"))
    )
    (net (code "42") (name "unconnected-(D1-IO-3-Pad4)") (class "Default")
      (node (ref "D1") (pin "4") (pinfunction "IO-3_4") (pintype "passive"))
    )
    (net (code "43") (name "unconnected-(D1-IO-4-Pad6)") (class "Default")
      (node (ref "D1") (pin "6") (pinfunction "IO-4_6") (pintype "passive"))
    )
    (net (code "44") (name "unconnected-(J1-ID-Pad4)") (class "Default")
      (node (ref "J1") (pin "4") (pinfunction "ID_4") (pintype "passive"))
    )
    (net (code "45") (name "unconnected-(J4-Pad1)") (class "Default")
      (node (ref "J4") (pin "1") (pinfunction "1_1") (pintype "passive"))
    )
    (net (code "46") (name "unconnected-(SW2-Pad1)") (class "Default")
      (node (ref "SW2") (pin "1") (pinfunction "1_1") (pintype "passive"))
    )
    (net (code "47") (name "unconnected-(SW2-Pad4)") (class "Default")
      (node (ref "SW2") (pin "4") (pinfunction "4_4") (pintype "passive"))
    )
    (net (code "48") (name "unconnected-(U1-CTS#-Pad9)") (class "Default")
      (node (ref "U1") (pin "9") (pinfunction "CTS#_9") (pintype "passive"))
    )
    (net (code "49") (name "unconnected-(U1-DCD#-Pad12)") (class "Default")
      (node (ref "U1") (pin "12") (pinfunction "DCD#_12") (pintype "passive"))
    )
    (net (code "50") (name "unconnected-(U1-DSR#-Pad10)") (class "Default")
      (node (ref "U1") (pin "10") (pinfunction "DSR#_10") (pintype "passive"))
    )
    (net (code "51") (name "unconnected-(U1-RI#-Pad11)") (class "Default")
      (node (ref "U1") (pin "11") (pinfunction "RI#_11") (pintype "passive"))
    )
    (net (code "52") (name "unconnected-(U1-RS232-Pad15)") (class "Default")
      (node (ref "U1") (pin "15") (pinfunction "RS232_15") (pintype "passive"))
    )
    (net (code "53") (name "unconnected-(U1-RTS#-Pad14)") (class "Default")
      (node (ref "U1") (pin "14") (pinfunction "RTS#_14") (pintype "passive"))
    )
    (net (code "54") (name "unconnected-(U2-ADC6-Pad19)") (class "Default")
      (node (ref "U2") (pin "19") (pinfunction "ADC6_19") (pintype "bidirectional"))
    )
    (net (code "55") (name "unconnected-(U2-ADC7-Pad22)") (class "Default")
      (node (ref "U2") (pin "22") (pinfunction "ADC7_22") (pintype "bidirectional"))
    )
  )
)
